# Sheet1.net
KiCad netlist of a schematic drawn in Altium Designer
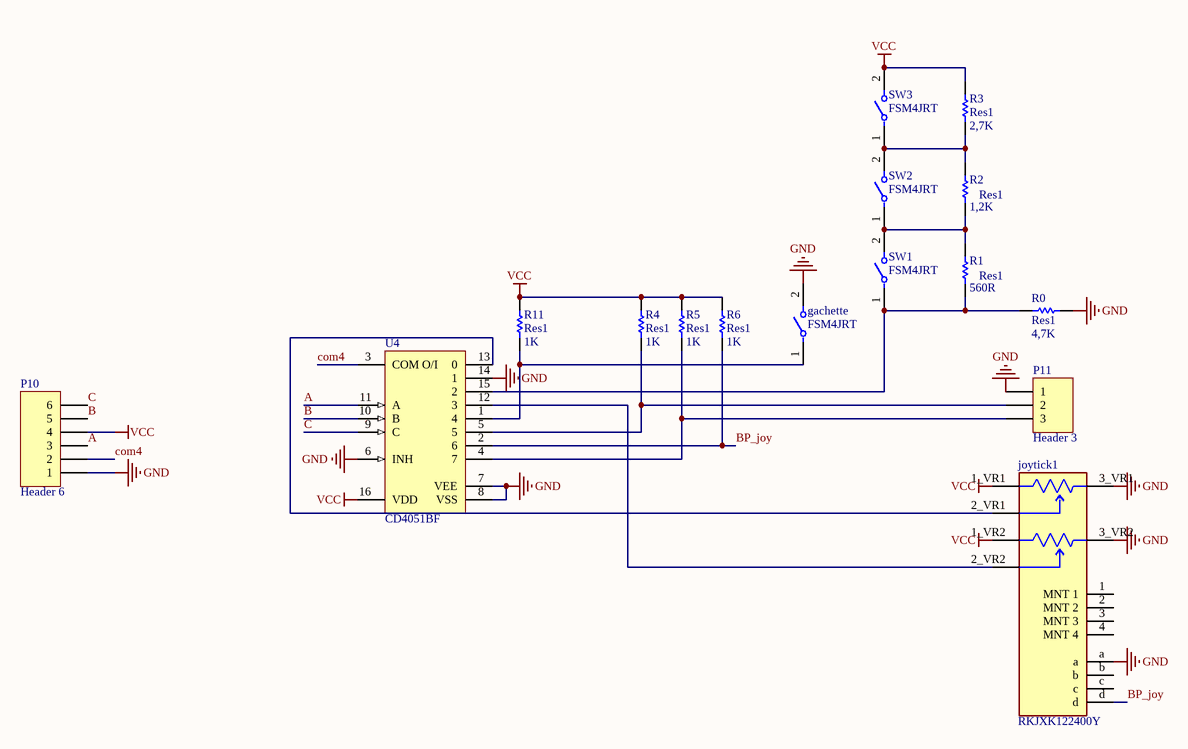
[diagram p0: Sheet1.SchDoc]

(export (version "E")
  (design (tool "Eeschema 10.0.6"))
  (components
    (comp (ref "gachette")
      (value "FSM4JRT")
      (footprint "FP-FSM4JRT-MFG")
      (description "SWITCH TACTILE SPST-NO 0.05A 24V")
      (libsource (lib "Altium Content Vault") (part "bb27bde45df87f1f469753f287ef5ae"))
    )
    (comp (ref "joytick1")
      (value "RKJXK122400Y")
      (footprint "FP-RKJXK122400Y-MFG")
      (description "Res POT 10K Ohm 0.0125W (25.4 X 20.7 X 19.3mm) Pin Bracket Mount/Through Hole Tray")
      (libsource (lib "Altium Content Vault") (part "63a56dd8e99e1e1552a3870b2e96c5c"))
    )
    (comp (ref "P10")
      (value "Header 6")
      (footprint "HDR1X6")
      (description "Header, 6-Pin")
      (fields (field (name "PUBLISHER") "Altium Limited"))
      (libsource (lib "Miscellaneous Connectors") (part "Header 6"))
    )
    (comp (ref "P11")
      (value "Header 3")
      (footprint "HDR1X3")
      (description "Header, 3-Pin")
      (fields (field (name "PUBLISHER") "Altium Limited"))
      (libsource (lib "Miscellaneous Connectors") (part "Header 3"))
    )
    (comp (ref "R0")
      (value "Res1")
      (footprint "AXIAL-0.3")
      (description "Resistor")
      (fields (field (name "ALTIUM_VALUE") "4,7K") (field (name "PUBLISHER") "Altium Limited"))
      (libsource (lib "Miscellaneous Devices") (part "Res1"))
    )
    (comp (ref "R1")
      (value "Res1")
      (footprint "AXIAL-0.3")
      (description "Resistor")
      (fields (field (name "ALTIUM_VALUE") "560R") (field (name "PUBLISHER") "Altium Limited"))
      (libsource (lib "Miscellaneous Devices") (part "Res1"))
    )
    (comp (ref "R2")
      (value "Res1")
      (footprint "AXIAL-0.3")
      (description "Resistor")
      (fields (field (name "ALTIUM_VALUE") "1,2K") (field (name "PUBLISHER") "Altium Limited"))
      (libsource (lib "Miscellaneous Devices") (part "Res1"))
    )
    (comp (ref "R3")
      (value "Res1")
      (footprint "AXIAL-0.3")
      (description "Resistor")
      (fields (field (name "ALTIUM_VALUE") "2,7K") (field (name "PUBLISHER") "Altium Limited"))
      (libsource (lib "Miscellaneous Devices") (part "Res1"))
    )
    (comp (ref "R4")
      (value "Res1")
      (footprint "AXIAL-0.3")
      (description "Resistor")
      (fields (field (name "ALTIUM_VALUE") "1K") (field (name "PUBLISHER") "Altium Limited"))
      (libsource (lib "Miscellaneous Devices") (part "Res1"))
    )
    (comp (ref "R5")
      (value "Res1")
      (footprint "AXIAL-0.3")
      (description "Resistor")
      (fields (field (name "ALTIUM_VALUE") "1K") (field (name "PUBLISHER") "Altium Limited"))
      (libsource (lib "Miscellaneous Devices") (part "Res1"))
    )
    (comp (ref "R6")
      (value "Res1")
      (footprint "AXIAL-0.3")
      (description "Resistor")
      (fields (field (name "ALTIUM_VALUE") "1K") (field (name "PUBLISHER") "Altium Limited"))
      (libsource (lib "Miscellaneous Devices") (part "Res1"))
    )
    (comp (ref "R11")
      (value "Res1")
      (footprint "AXIAL-0.3")
      (description "Resistor")
      (fields (field (name "ALTIUM_VALUE") "1K") (field (name "PUBLISHER") "Altium Limited"))
      (libsource (lib "Miscellaneous Devices") (part "Res1"))
    )
    (comp (ref "SW1")
      (value "FSM4JRT")
      (footprint "FP-FSM4JRT-MFG")
      (description "SWITCH TACTILE SPST-NO 0.05A 24V")
      (libsource (lib "Altium Content Vault") (part "bb27bde45df87f1f469753f287ef5ae"))
    )
    (comp (ref "SW2")
      (value "FSM4JRT")
      (footprint "FP-FSM4JRT-MFG")
      (description "SWITCH TACTILE SPST-NO 0.05A 24V")
      (libsource (lib "Altium Content Vault") (part "bb27bde45df87f1f469753f287ef5ae"))
    )
    (comp (ref "SW3")
      (value "FSM4JRT")
      (footprint "FP-FSM4JRT-MFG")
      (description "SWITCH TACTILE SPST-NO 0.05A 24V")
      (libsource (lib "Altium Content Vault") (part "bb27bde45df87f1f469753f287ef5ae"))
    )
    (comp (ref "U4")
      (value "CD4051BF")
      (footprint "J0016A")
      (description "CMOS Single 8-Channel Analog Multiplexer/Demultiplexer with Logic-Level Conversion, J0016A, TUBE")
      (fields
        (field (name "GENERIC PART NUMBER") "CD4051B-MIL")
        (field (name "MANUFACTURER") "Texas Instruments")
      )
      (libsource (lib "Altium Content Vault") (part "TI-CD4051B-16"))
    )
  )
  (nets
    (net (code "1") (name "/A") (class "Default")
      (node (ref "P10") (pin "3") (pinfunction "3_3") (pintype "passive"))
      (node (ref "U4") (pin "11") (pinfunction "A_11") (pintype "input"))
    )
    (net (code "2") (name "/B") (class "Default")
      (node (ref "P10") (pin "5") (pinfunction "5_5") (pintype "passive"))
      (node (ref "U4") (pin "10") (pinfunction "B_10") (pintype "input"))
    )
    (net (code "3") (name "/BP_joy") (class "Default")
      (node (ref "R6") (pin "1") (pinfunction "1_1") (pintype "passive"))
      (node (ref "U4") (pin "2") (pinfunction "6_2") (pintype "passive"))
      (node (ref "joytick1") (pin "d") (pinfunction "d_d") (pintype "passive"))
    )
    (net (code "4") (name "/C") (class "Default")
      (node (ref "P10") (pin "6") (pinfunction "6_6") (pintype "passive"))
      (node (ref "U4") (pin "9") (pinfunction "C_9") (pintype "input"))
    )
    (net (code "5") (name "/com4") (class "Default")
      (node (ref "P10") (pin "2") (pinfunction "2_2") (pintype "passive"))
      (node (ref "U4") (pin "3") (pinfunction "COM_O/I_3") (pintype "passive"))
    )
    (net (code "6") (name "GND") (class "Default")
      (node (ref "P10") (pin "1") (pinfunction "1_1") (pintype "passive"))
      (node (ref "P11") (pin "1") (pinfunction "1_1") (pintype "passive"))
      (node (ref "R0") (pin "1") (pinfunction "1_1") (pintype "passive"))
      (node (ref "U4") (pin "14") (pinfunction "1_14") (pintype "passive"))
      (node (ref "U4") (pin "6") (pinfunction "INH_6") (pintype "input"))
      (node (ref "U4") (pin "7") (pinfunction "VEE_7") (pintype "power_in"))
      (node (ref "U4") (pin "8") (pinfunction "VSS_8") (pintype "power_in"))
      (node (ref "gachette") (pin "2") (pinfunction "2_2") (pintype "passive"))
      (node (ref "joytick1") (pin "3_VR1") (pinfunction "3_VR1_3_VR1") (pintype "passive"))
      (node (ref "joytick1") (pin "3_VR2") (pinfunction "3_VR2_3_VR2") (pintype "passive"))
      (node (ref "joytick1") (pin "a") (pinfunction "a_a") (pintype "passive"))
    )
    (net (code "7") (name "Net-(P11-Pad2)") (class "Default")
      (node (ref "P11") (pin "2") (pinfunction "2_2") (pintype "passive"))
      (node (ref "R4") (pin "1") (pinfunction "1_1") (pintype "passive"))
      (node (ref "U4") (pin "5") (pinfunction "5_5") (pintype "passive"))
    )
    (net (code "8") (name "Net-(R1-Pad2)") (class "Default")
      (node (ref "R1") (pin "2") (pinfunction "2_2") (pintype "passive"))
      (node (ref "R2") (pin "1") (pinfunction "1_1") (pintype "passive"))
      (node (ref "SW1") (pin "2") (pinfunction "2_2") (pintype "passive"))
      (node (ref "SW2") (pin "1") (pinfunction "1_1") (pintype "passive"))
    )
    (net (code "9") (name "Net-(R2-Pad2)") (class "Default")
      (node (ref "R2") (pin "2") (pinfunction "2_2") (pintype "passive"))
      (node (ref "R3") (pin "1") (pinfunction "1_1") (pintype "passive"))
      (node (ref "SW2") (pin "2") (pinfunction "2_2") (pintype "passive"))
      (node (ref "SW3") (pin "1") (pinfunction "1_1") (pintype "passive"))
    )
    (net (code "10") (name "Net-(U4-0)") (class "Default")
      (node (ref "U4") (pin "13") (pinfunction "0_13") (pintype "passive"))
      (node (ref "joytick1") (pin "2_VR1") (pinfunction "2_VR1_2_VR1") (pintype "passive"))
    )
    (net (code "11") (name "Net-(U4-2)") (class "Default")
      (node (ref "R0") (pin "2") (pinfunction "2_2") (pintype "passive"))
      (node (ref "R1") (pin "1") (pinfunction "1_1") (pintype "passive"))
      (node (ref "SW1") (pin "1") (pinfunction "1_1") (pintype "passive"))
      (node (ref "U4") (pin "15") (pinfunction "2_15") (pintype "passive"))
    )
    (net (code "12") (name "Net-(U4-3)") (class "Default")
      (node (ref "U4") (pin "12") (pinfunction "3_12") (pintype "passive"))
      (node (ref "joytick1") (pin "2_VR2") (pinfunction "2_VR2_2_VR2") (pintype "passive"))
    )
    (net (code "13") (name "Net-(U4-4)") (class "Default")
      (node (ref "R11") (pin "1") (pinfunction "1_1") (pintype "passive"))
      (node (ref "U4") (pin "1") (pinfunction "4_1") (pintype "passive"))
      (node (ref "gachette") (pin "1") (pinfunction "1_1") (pintype "passive"))
    )
    (net (code "14") (name "Net-(U4-7)") (class "Default")
      (node (ref "P11") (pin "3") (pinfunction "3_3") (pintype "passive"))
      (node (ref "R5") (pin "1") (pinfunction "1_1") (pintype "passive"))
      (node (ref "U4") (pin "4") (pinfunction "7_4") (pintype "passive"))
    )
    (net (code "15") (name "VCC") (class "Default")
      (node (ref "P10") (pin "4") (pinfunction "4_4") (pintype "passive"))
      (node (ref "R11") (pin "2") (pinfunction "2_2") (pintype "passive"))
      (node (ref "R3") (pin "2") (pinfunction "2_2") (pintype "passive"))
      (node (ref "R4") (pin "2") (pinfunction "2_2") (pintype "passive"))
      (node (ref "R5") (pin "2") (pinfunction "2_2") (pintype "passive"))
      (node (ref "R6") (pin "2") (pinfunction "2_2") (pintype "passive"))
      (node (ref "SW3") (pin "2") (pinfunction "2_2") (pintype "passive"))
      (node (ref "U4") (pin "16") (pinfunction "VDD_16") (pintype "power_in"))
      (node (ref "joytick1") (pin "1_VR1") (pinfunction "1_VR1_1_VR1") (pintype "passive"))
      (node (ref "joytick1") (pin "1_VR2") (pinfunction "1_VR2_1_VR2") (pintype "passive"))
    )
    (net (code "16") (name "unconnected-(joytick1-MNT_1-Pad1)") (class "Default")
      (node (ref "joytick1") (pin "1") (pinfunction "MNT_1_1") (pintype "passive"))
    )
    (net (code "17") (name "unconnected-(joytick1-MNT_2-Pad2)") (class "Default")
      (node (ref "joytick1") (pin "2") (pinfunction "MNT_2_2") (pintype "passive"))
    )
    (net (code "18") (name "unconnected-(joytick1-MNT_3-Pad3)") (class "Default")
      (node (ref "joytick1") (pin "3") (pinfunction "MNT_3_3") (pintype "passive"))
    )
    (net (code "19") (name "unconnected-(joytick1-MNT_4-Pad4)") (class "Default")
      (node (ref "joytick1") (pin "4") (pinfunction "MNT_4_4") (pintype "passive"))
    )
    (net (code "20") (name "unconnected-(joytick1-Padb)") (class "Default")
      (node (ref "joytick1") (pin "b") (pinfunction "b_b") (pintype "passive"))
    )
    (net (code "21") (name "unconnected-(joytick1-Padc)") (class "Default")
      (node (ref "joytick1") (pin "c") (pinfunction "c_c") (pintype "passive"))
    )
  )
)
